# flyback.net
KiCad netlist of a schematic drawn in Altium Designer
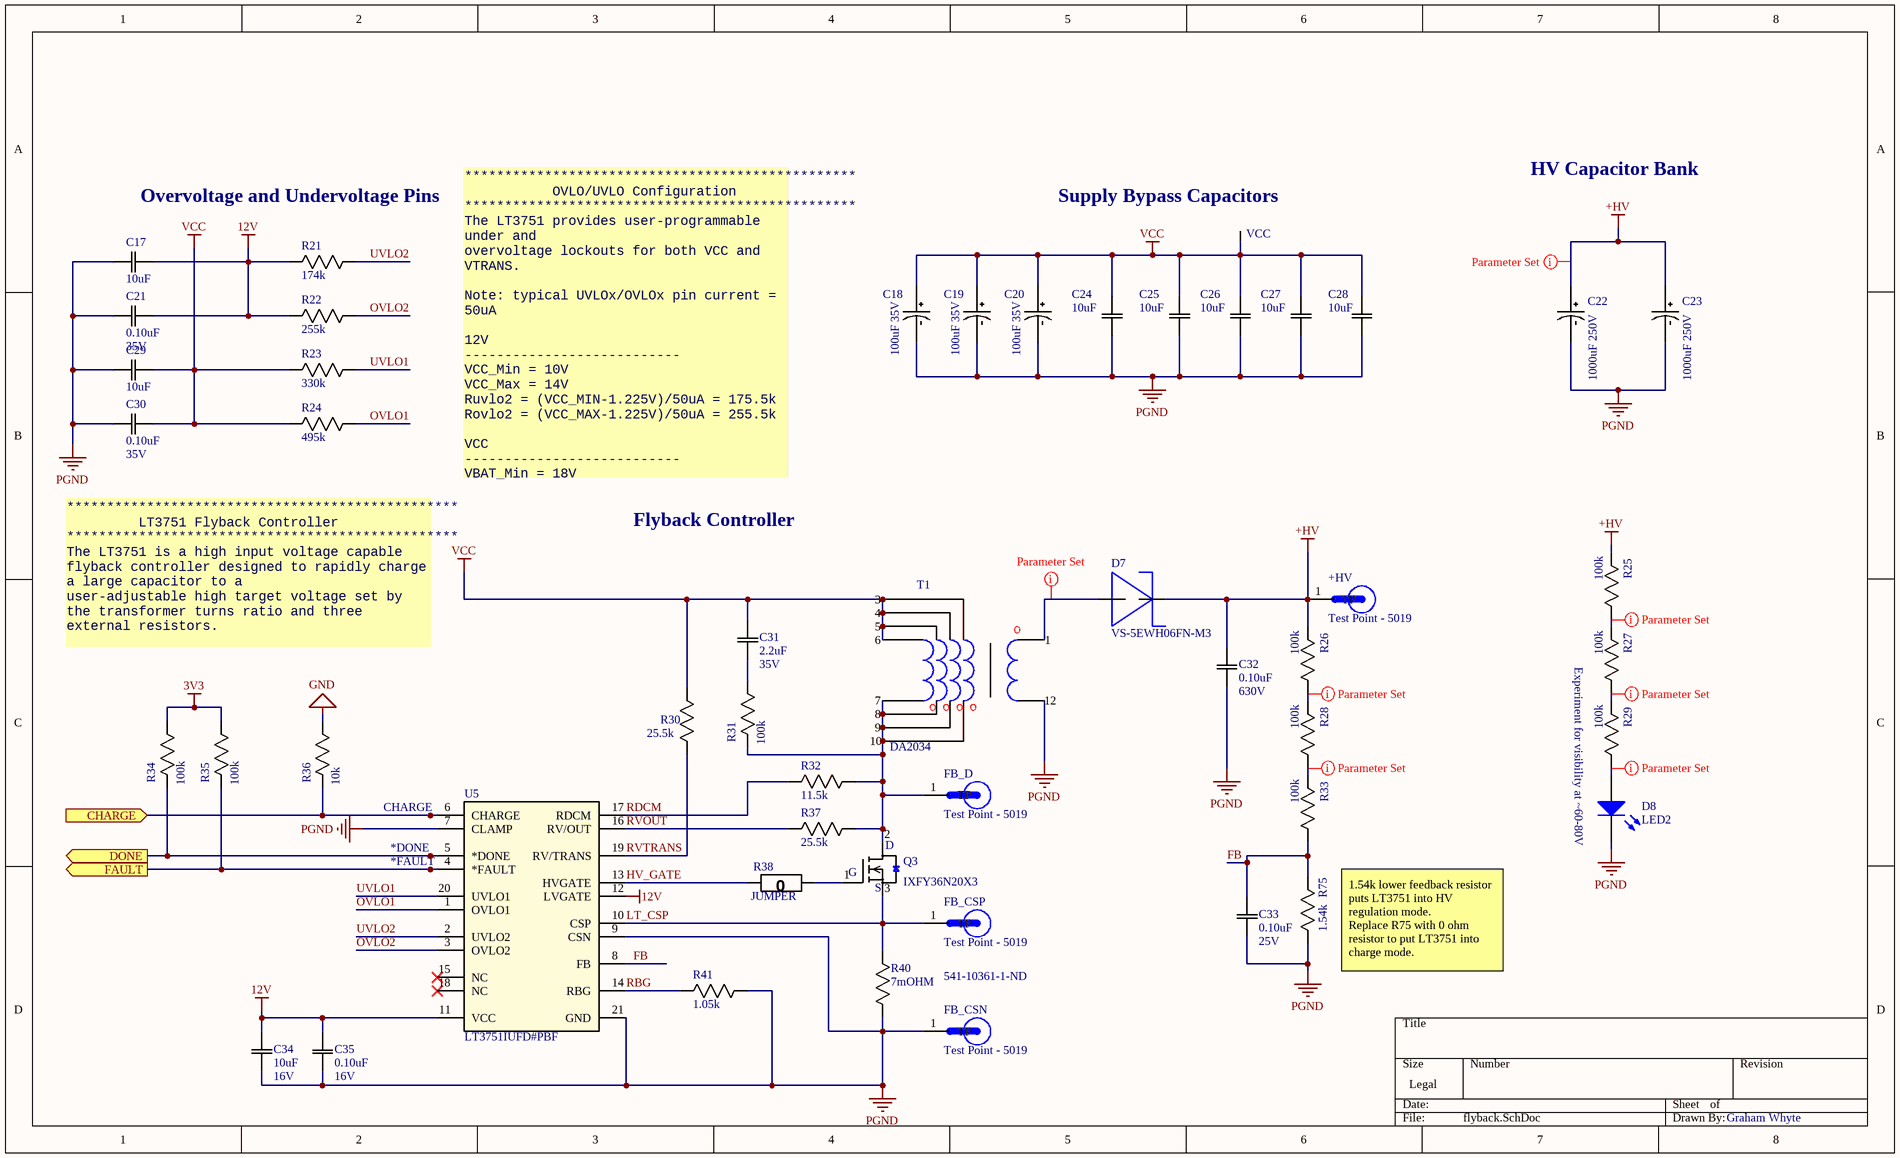
[diagram p0: flyback.SchDoc]

(export (version "E")
  (design (tool "Eeschema 10.0.6"))
  (components
    (comp (ref "*DONE")
      (value "Test Point (Via)")
      (footprint "TP")
      (libsource (lib "IC_Library") (part "Test Point (Via)"))
    )
    (comp (ref "*FAULT")
      (value "Test Point (Via)")
      (footprint "TP")
      (libsource (lib "IC_Library") (part "Test Point (Via)"))
    )
    (comp (ref "+HV")
      (value "Test Point - 5019")
      (footprint "TP380X203")
      (description "PC Test Point, Miniature Phosphor Bronze, Silver Plating Surface Mount Mounting Type")
      (fields (field (name "MP") "5019") (field (name "MF") "Keystone Electronics"))
      (libsource (lib "IC_Library") (part "Test Point - 5019"))
    )
    (comp (ref "C17")
      (value "10uF")
      (footprint "0805")
      (description "CAP CER 10UF 35V X7R 0805")
      (fields (field (name "TOLERANCE") "10%") (field (name "PART NUMBER") "CAP 10uF 35V"))
      (libsource (lib "capacitor_library") (part "CAP 10uF 35V"))
    )
    (comp (ref "C18")
      (value "100uF 35V")
      (footprint "CAP POL ALU 6.3x5.8")
      (description "CAP ALUM 100UF 35V SMD")
      (fields (field (name "TOLERANCE") "20%") (field (name "PART NUMBER") "CAP POL 100uF SMD"))
      (libsource (lib "capacitor_library") (part "CAP POL 100uF SMD"))
    )
    (comp (ref "C19")
      (value "100uF 35V")
      (footprint "CAP POL ALU 6.3x5.8")
      (description "CAP ALUM 100UF 35V SMD")
      (fields (field (name "TOLERANCE") "20%") (field (name "PART NUMBER") "CAP POL 100uF SMD"))
      (libsource (lib "capacitor_library") (part "CAP POL 100uF SMD"))
    )
    (comp (ref "C20")
      (value "100uF 35V")
      (footprint "CAP POL ALU 6.3x5.8")
      (description "CAP ALUM 100UF 35V SMD")
      (fields (field (name "TOLERANCE") "20%") (field (name "PART NUMBER") "CAP POL 100uF SMD"))
      (libsource (lib "capacitor_library") (part "CAP POL 100uF SMD"))
    )
    (comp (ref "C21")
      (value "0.10uF")
      (footprint "0805")
      (description "CAP CER 0.10UF 35V X7R 0805")
      (fields
        (field (name "TOLERANCE") "10%")
        (field (name "RATING") "35V")
        (field (name "PART NUMBER") "CAP 0.10uF 35V")
      )
      (libsource (lib "capacitor_library") (part "CAP 0.10uF 35V"))
    )
    (comp (ref "C22")
      (value "1000uF 250V")
      (footprint "RADIAL, CAN - THRU 25.4mm")
      (description "United Chemi-Con\r\nESMQ251VSN102MQ45S")
      (fields
        (field (name "MANUFACTURER") "United Chemi-Con")
        (field (name "MANUFACTURER PART NUMBER") "ESMQ251VSN102MQ45S")
      )
      (libsource (lib "capacitor_library") (part "CAP POL 1000uF"))
    )
    (comp (ref "C23")
      (value "1000uF 250V")
      (footprint "RADIAL, CAN - THRU 25.4mm")
      (description "United Chemi-Con\r\nESMQ251VSN102MQ45S")
      (fields
        (field (name "MANUFACTURER") "United Chemi-Con")
        (field (name "MANUFACTURER PART NUMBER") "ESMQ251VSN102MQ45S")
      )
      (libsource (lib "capacitor_library") (part "CAP POL 1000uF"))
    )
    (comp (ref "C24")
      (value "10uF")
      (footprint "0805")
      (description "CAP CER 10UF 35V X7R 0805")
      (fields (field (name "TOLERANCE") "10%") (field (name "PART NUMBER") "CAP 10uF 35V"))
      (libsource (lib "capacitor_library") (part "CAP 10uF 35V"))
    )
    (comp (ref "C25")
      (value "10uF")
      (footprint "0805")
      (description "CAP CER 10UF 35V X7R 0805")
      (fields (field (name "TOLERANCE") "10%") (field (name "PART NUMBER") "CAP 10uF 35V"))
      (libsource (lib "capacitor_library") (part "CAP 10uF 35V"))
    )
    (comp (ref "C26")
      (value "10uF")
      (footprint "0805")
      (description "CAP CER 10UF 35V X7R 0805")
      (fields (field (name "TOLERANCE") "10%") (field (name "PART NUMBER") "CAP 10uF 35V"))
      (libsource (lib "capacitor_library") (part "CAP 10uF 35V"))
    )
    (comp (ref "C27")
      (value "10uF")
      (footprint "0805")
      (description "CAP CER 10UF 35V X7R 0805")
      (fields (field (name "TOLERANCE") "10%") (field (name "PART NUMBER") "CAP 10uF 35V"))
      (libsource (lib "capacitor_library") (part "CAP 10uF 35V"))
    )
    (comp (ref "C28")
      (value "10uF")
      (footprint "0805")
      (description "CAP CER 10UF 35V X7R 0805")
      (fields (field (name "TOLERANCE") "10%") (field (name "PART NUMBER") "CAP 10uF 35V"))
      (libsource (lib "capacitor_library") (part "CAP 10uF 35V"))
    )
    (comp (ref "C29")
      (value "10uF")
      (footprint "0805")
      (description "CAP CER 10UF 35V X7R 0805")
      (fields (field (name "TOLERANCE") "10%") (field (name "PART NUMBER") "CAP 10uF 35V"))
      (libsource (lib "capacitor_library") (part "CAP 10uF 35V"))
    )
    (comp (ref "C30")
      (value "0.10uF")
      (footprint "0805")
      (description "CAP CER 0.10UF 35V X7R 0805")
      (fields
        (field (name "TOLERANCE") "10%")
        (field (name "RATING") "35V")
        (field (name "PART NUMBER") "CAP 0.10uF 35V")
      )
      (libsource (lib "capacitor_library") (part "CAP 0.10uF 35V"))
    )
    (comp (ref "C31")
      (value "2.2uF")
      (footprint "0603")
      (description "CAP CER 2.2UF 35V X7R 0603/0805")
      (fields
        (field (name "TOLERANCE") "10%")
        (field (name "RATING") "35V")
        (field (name "PART NUMBER") "CAP 2.2uF 35V")
      )
      (libsource (lib "capacitor_library") (part "CAP 2.2uF 35V"))
    )
    (comp (ref "C32")
      (value "0.10uF")
      (footprint "1210")
      (description "CAP CER 0.1uF 630V X7R 1210")
      (fields
        (field (name "TOLERANCE") "10%")
        (field (name "RATING") "630V")
        (field (name "PART NUMBER") "CAP 0.10uF 630V")
      )
      (libsource (lib "capacitor_library") (part "CAP 0.10uF 630V"))
    )
    (comp (ref "C33")
      (value "0.10uF")
      (footprint "0805")
      (description "CAP CER 0.10UF 25V X7R 0805")
      (fields
        (field (name "TOLERANCE") "10%")
        (field (name "RATING") "25V")
        (field (name "PART NUMBER") "CAP 0.10uF 25V")
      )
      (libsource (lib "capacitor_library") (part "CAP 0.10uF 25V"))
    )
    (comp (ref "C34")
      (value "10uF")
      (footprint "0603")
      (description "CAP CER 10UF 16V X5R 0603/0805")
      (fields
        (field (name "TOLERANCE") "10%")
        (field (name "RATING") "16V")
        (field (name "PART NUMBER") "CAP 10uF 16V")
      )
      (libsource (lib "capacitor_library") (part "CAP 10uF 16V"))
    )
    (comp (ref "C35")
      (value "0.10uF")
      (footprint "0603")
      (description "CAP CER 0.10UF 16V X5R 0603")
      (fields
        (field (name "TOLERANCE") "10%")
        (field (name "RATING") "16V")
        (field (name "PART NUMBER") "CAP 0.10uF 16V")
      )
      (libsource (lib "capacitor_library") (part "CAP 0.10uF 16V"))
    )
    (comp (ref "CHARGE")
      (value "Test Point (Via)")
      (footprint "TP")
      (libsource (lib "IC_Library") (part "Test Point (Via)"))
    )
    (comp (ref "D7")
      (value "VS-5EWH06FN-M3")
      (footprint "DPAK (TO-252)")
      (description "Diode Switching 600V 5A DPAK")
      (fields (field (name "MF") "Vishay Diodes"))
      (libsource (lib "Diode_Library") (part "VS-5EWH06FN-M3"))
    )
    (comp (ref "D8")
      (value "LED2")
      (footprint "3.2X1.6X1.1")
      (description "Typical RED, GREEN, YELLOW, AMBER GaAs LED")
      (fields (field (name "PART NUMBER") "LED GREEN SMD"))
      (libsource (lib "Diode_Library") (part "LED GREEN SMD"))
    )
    (comp (ref "FB_CSN")
      (value "Test Point - 5019")
      (footprint "TP380X203")
      (description "PC Test Point, Miniature Phosphor Bronze, Silver Plating Surface Mount Mounting Type")
      (fields (field (name "MP") "5019") (field (name "MF") "Keystone Electronics"))
      (libsource (lib "IC_Library") (part "Test Point - 5019"))
    )
    (comp (ref "FB_CSP")
      (value "Test Point - 5019")
      (footprint "TP380X203")
      (description "PC Test Point, Miniature Phosphor Bronze, Silver Plating Surface Mount Mounting Type")
      (fields (field (name "MP") "5019") (field (name "MF") "Keystone Electronics"))
      (libsource (lib "IC_Library") (part "Test Point - 5019"))
    )
    (comp (ref "FB_D")
      (value "Test Point - 5019")
      (footprint "TP380X203")
      (description "PC Test Point, Miniature Phosphor Bronze, Silver Plating Surface Mount Mounting Type")
      (fields (field (name "MP") "5019") (field (name "MF") "Keystone Electronics"))
      (libsource (lib "IC_Library") (part "Test Point - 5019"))
    )
    (comp (ref "Q3")
      (value "IXFY36N20X3")
      (footprint "DPAK (TO-252)")
      (description "N-Channel 200 V 36A (Tc) 176W (Tc) Surface Mount TO-252AA")
      (fields (field (name "PART NUMBER") "MOSFET N-CH IXFY36N20X3"))
      (libsource (lib "Transistor_Library") (part "MOSFET N-CH IXFY36N20X3"))
    )
    (comp (ref "R21")
      (value "174k")
      (footprint "0603")
      (description "RES SMD 174K OHM 1% 1/8W 0603")
      (fields
        (field (name "MANUFACTURER") "Yageo")
        (field (name "MANUFACTURER PART NUMBER") "RC0805FR-07174KL")
      )
      (libsource (lib "Resistor_Library") (part "RES 174k 1/8W"))
    )
    (comp (ref "R22")
      (value "255k")
      (footprint "0603")
      (description "RES 255k 1/8W - 1% 0603")
      (fields (field (name "PART NUMBER") "RES 255k 1/8W - 1%"))
      (libsource (lib "Resistor_Library") (part "RES 255k 1/8W - 1%"))
    )
    (comp (ref "R23")
      (value "330k")
      (footprint "0603")
      (description "RES SMD 274K OHM 1% 1/8W 0603")
      (fields (field (name "PART NUMBER") "RES 330k 1/8W - 1%"))
      (libsource (lib "Resistor_Library") (part "RES 330k 1/8W - 1%"))
    )
    (comp (ref "R24")
      (value "495k")
      (footprint "0603")
      (description "RES SMD 495K OHM 1% 1/8W 0603")
      (fields
        (field (name "MANUFACTURER") "Yageo")
        (field (name "MANUFACTURER PART NUMBER") "RC0805FR-07499KL")
      )
      (libsource (lib "Resistor_Library") (part "RES 495k 1/8W"))
    )
    (comp (ref "R25")
      (value "100k")
      (footprint "0603")
      (description "RES SMD 100K OHM 5% 1/8W 0603")
      (fields (field (name "TOLERANCE") "5%") (field (name "PART NUMBER") "RES 100k 1/8W - 5%"))
      (libsource (lib "") (part "RES 100k 1/8W 5%_1"))
    )
    (comp (ref "R26")
      (value "100k")
      (footprint "0603")
      (description "RES SMD 100K OHM 1% 1/8W 0603")
      (fields (field (name "TOLERANCE") "1%") (field (name "PART NUMBER") "RES 100k 1/8W - 1%"))
      (libsource (lib "Resistor_Library") (part "RES 100k 1/8W 1%"))
    )
    (comp (ref "R27")
      (value "100k")
      (footprint "0603")
      (description "RES SMD 100K OHM 5% 1/8W 0603")
      (fields (field (name "TOLERANCE") "5%") (field (name "PART NUMBER") "RES 100k 1/8W - 5%"))
      (libsource (lib "Resistor_Library") (part "RES 100k 1/8W 5%"))
    )
    (comp (ref "R28")
      (value "100k")
      (footprint "0603")
      (description "RES SMD 100K OHM 1% 1/8W 0603")
      (fields (field (name "TOLERANCE") "1%") (field (name "PART NUMBER") "RES 100k 1/8W - 1%"))
      (libsource (lib "") (part "RES 100k 1/8W 1%_1"))
    )
    (comp (ref "R29")
      (value "100k")
      (footprint "0603")
      (description "RES SMD 100K OHM 5% 1/8W 0603")
      (fields (field (name "TOLERANCE") "5%") (field (name "PART NUMBER") "RES 100k 1/8W - 5%"))
      (libsource (lib "Resistor_Library") (part "RES 100k 1/8W 5%"))
    )
    (comp (ref "R30")
      (value "25.5k")
      (footprint "0603")
      (description "RES SMD 25.5K OHM 0.1% 1/8W 0603")
      (fields
        (field (name "MANUFACTURER") "Panasonic")
        (field (name "MANUFACTURER PART NUMBER") "ERA-6AEB2552V")
      )
      (libsource (lib "Resistor_Library") (part "RES 25.5k 1/8W"))
    )
    (comp (ref "R31")
      (value "100k")
      (footprint "0603")
      (description "RES SMD 100K OHM 1% 1/8W 0603")
      (fields (field (name "TOLERANCE") "1%") (field (name "PART NUMBER") "RES 100k 1/8W - 1%"))
      (libsource (lib "Resistor_Library") (part "RES 100k 1/8W 1%"))
    )
    (comp (ref "R32")
      (value "11.5k")
      (footprint "0603")
      (description "RES SMD 11.5K OHM 0.1% 1/8W 0603 Thin Film")
      (fields
        (field (name "MANUFACTURER") "Panasonic")
        (field (name "MANUFACTURER PART NUMBER") "ERA-6AEB1152V")
      )
      (libsource (lib "Resistor_Library") (part "RES 11.5k 1/8W"))
    )
    (comp (ref "R33")
      (value "100k")
      (footprint "0603")
      (description "RES SMD 100K OHM 1% 1/8W 0603")
      (fields (field (name "TOLERANCE") "1%") (field (name "PART NUMBER") "RES 100k 1/8W - 1%"))
      (libsource (lib "") (part "RES 100k 1/8W 1%_1"))
    )
    (comp (ref "R34")
      (value "100k")
      (footprint "0603")
      (description "RES SMD 100K OHM 5% 1/8W 0603")
      (fields (field (name "TOLERANCE") "5%") (field (name "PART NUMBER") "RES 100k 1/8W - 5%"))
      (libsource (lib "Resistor_Library") (part "RES 100k 1/8W 5%"))
    )
    (comp (ref "R35")
      (value "100k")
      (footprint "0603")
      (description "RES SMD 100K OHM 5% 1/8W 0603")
      (fields (field (name "TOLERANCE") "5%") (field (name "PART NUMBER") "RES 100k 1/8W - 5%"))
      (libsource (lib "Resistor_Library") (part "RES 100k 1/8W 5%"))
    )
    (comp (ref "R36")
      (value "10k")
      (footprint "0603")
      (description "RES SMD 10K OHM 5% 1/8W 0603")
      (fields (field (name "TOLERANCE") "5%") (field (name "PART NUMBER") "RES 10k 1/8W - 5%"))
      (libsource (lib "Resistor_Library") (part "RES 10k 1/8W 5%"))
    )
    (comp (ref "R37")
      (value "25.5k")
      (footprint "0603")
      (description "RES SMD 25.5K OHM 0.1% 1/8W 0603")
      (fields
        (field (name "MANUFACTURER") "Panasonic")
        (field (name "MANUFACTURER PART NUMBER") "ERA-6AEB2552V")
      )
      (libsource (lib "Resistor_Library") (part "RES 25.5k 1/8W"))
    )
    (comp (ref "R38")
      (value "JUMPER")
      (footprint "0603")
      (description "RES SMD 0 OHM JUMPER GENERIC 0603")
      (fields (field (name "PART NUMBER") "RES 0 JUMPER"))
      (libsource (lib "Resistor_Library") (part "RES 0 JUMPER"))
    )
    (comp (ref "R40")
      (value "7mOHM")
      (footprint "2512")
      (description "RES SMD 7m OHM 1% 3W 2512")
      (fields
        (field (name "TOLERANCE") "1%")
        (field (name "MFG") "VISHAY")
        (field (name "SUPPLIER PART NUMBER 1") "541-10361-1-ND")
      )
      (libsource (lib "Resistor_Library") (part "RES 7m 3W"))
    )
    (comp (ref "R41")
      (value "1.05k")
      (footprint "0603")
      (description "RES SMD 1.05K OHM 0.1% 1/8W 0603")
      (fields (field (name "TOLERANCE") "0.1%") (field (name "PART NUMBER") "RES 1.05k 1/8W"))
      (libsource (lib "Resistor_Library") (part "RES 1.05k 1/8W"))
    )
    (comp (ref "R75")
      (value "1.54k")
      (footprint "0603")
      (description "RES SMD 1.54k OHM 1% 1/8W 0603")
      (fields (field (name "TOLERANCE") "1%") (field (name "PART NUMBER") "RES 1.54k 1_8W - 1%"))
      (libsource (lib "Resistor_Library") (part "RES 1.54k 1/8W - 1%"))
    )
    (comp (ref "T1")
      (value "DA2034")
      (footprint "DA2034")
      (description "Audio Transformers / Signal Transformers DA2032 Cap Chrgr For Linear LT3750/51")
      (libsource (lib "IC_Library") (part "DA2034"))
    )
    (comp (ref "U5")
      (value "LT3751IUFD#PBF")
      (footprint "QFN-20_UFD_LIT-M")
      (description "IC CTRLR CAP CHRGR 4.75V 20-QFN")
      (fields
        (field (name "MANUFACTURER_PART_NUMBER") "lt3751iufd#pbf")
        (field (name "COPYRIGHT") "Copyright (C) 2021 Ultra Librarian. All rights reserved.")
      )
      (libsource (lib "IC_Library") (part "LT3751IUFD#PBF"))
    )
    (comp (ref "VCC")
      (value "Test Point (Via)")
      (footprint "TP")
      (libsource (lib "IC_Library") (part "Test Point (Via)"))
    )
  )
  (nets
    (net (code "1") (name "+HV") (class "Default")
      (node (ref "+HV") (pin "1") (pinfunction "TP_1") (pintype "passive"))
      (node (ref "C22") (pin "POS") (pinfunction "POS_POS") (pintype "passive"))
      (node (ref "C23") (pin "POS") (pinfunction "POS_POS") (pintype "passive"))
      (node (ref "C32") (pin "1") (pinfunction "C1_1") (pintype "passive"))
      (node (ref "D7") (pin "OUT") (pinfunction "OUT_OUT") (pintype "passive"))
      (node (ref "R25") (pin "2") (pinfunction "R2_2") (pintype "passive"))
      (node (ref "R26") (pin "2") (pinfunction "R2_2") (pintype "passive"))
    )
    (net (code "3") (name "/CHARGE") (class "Default")
      (node (ref "CHARGE") (pin "1") (pinfunction "1_1") (pintype "passive"))
      (node (ref "R36") (pin "2") (pinfunction "R2_2") (pintype "passive"))
      (node (ref "U5") (pin "6") (pinfunction "CHARGE_6") (pintype "passive"))
    )
    (net (code "4") (name "/DONE") (class "Default")
      (node (ref "*DONE") (pin "1") (pinfunction "1_1") (pintype "passive"))
      (node (ref "R34") (pin "2") (pinfunction "R2_2") (pintype "passive"))
      (node (ref "U5") (pin "5") (pinfunction "*DONE_5") (pintype "passive"))
    )
    (net (code "5") (name "/FAULT") (class "Default")
      (node (ref "*FAULT") (pin "1") (pinfunction "1_1") (pintype "passive"))
      (node (ref "R35") (pin "2") (pinfunction "R2_2") (pintype "passive"))
      (node (ref "U5") (pin "4") (pinfunction "*FAULT_4") (pintype "passive"))
    )
    (net (code "6") (name "/FB") (class "Default")
      (node (ref "C33") (pin "1") (pinfunction "C1_1") (pintype "passive"))
      (node (ref "R33") (pin "1") (pinfunction "R1_1") (pintype "passive"))
      (node (ref "R75") (pin "2") (pinfunction "R2_2") (pintype "passive"))
      (node (ref "U5") (pin "8") (pinfunction "FB_8") (pintype "passive"))
    )
    (net (code "7") (name "/HV_GATE") (class "Default")
      (node (ref "R38") (pin "2") (pinfunction "R2_2") (pintype "passive"))
      (node (ref "U5") (pin "13") (pinfunction "HVGATE_13") (pintype "passive"))
    )
    (net (code "8") (name "/LT_CSP") (class "Default")
      (node (ref "FB_CSP") (pin "1") (pinfunction "TP_1") (pintype "passive"))
      (node (ref "Q3") (pin "3") (pinfunction "S_3") (pintype "passive"))
      (node (ref "R40") (pin "2") (pinfunction "R2_2") (pintype "passive"))
      (node (ref "U5") (pin "10") (pinfunction "CSP_10") (pintype "passive"))
    )
    (net (code "9") (name "/OVLO1") (class "Default")
      (node (ref "R24") (pin "1") (pinfunction "R1_1") (pintype "passive"))
      (node (ref "U5") (pin "1") (pinfunction "OVLO1_1") (pintype "passive"))
    )
    (net (code "10") (name "/OVLO2") (class "Default")
      (node (ref "R22") (pin "1") (pinfunction "R1_1") (pintype "passive"))
      (node (ref "U5") (pin "3") (pinfunction "OVLO2_3") (pintype "passive"))
    )
    (net (code "11") (name "/RBG") (class "Default")
      (node (ref "R41") (pin "2") (pinfunction "R2_2") (pintype "passive"))
      (node (ref "U5") (pin "14") (pinfunction "RBG_14") (pintype "passive"))
    )
    (net (code "12") (name "/RDCM") (class "Default")
      (node (ref "R32") (pin "2") (pinfunction "R2_2") (pintype "passive"))
      (node (ref "U5") (pin "17") (pinfunction "RDCM_17") (pintype "passive"))
    )
    (net (code "13") (name "/RVOUT") (class "Default")
      (node (ref "R37") (pin "2") (pinfunction "R2_2") (pintype "passive"))
      (node (ref "U5") (pin "16") (pinfunction "RV/OUT_16") (pintype "passive"))
    )
    (net (code "14") (name "/RVTRANS") (class "Default")
      (node (ref "R30") (pin "2") (pinfunction "R2_2") (pintype "passive"))
      (node (ref "U5") (pin "19") (pinfunction "RV/TRANS_19") (pintype "passive"))
    )
    (net (code "15") (name "/UVLO1") (class "Default")
      (node (ref "R23") (pin "1") (pinfunction "R1_1") (pintype "passive"))
      (node (ref "U5") (pin "20") (pinfunction "UVLO1_20") (pintype "passive"))
    )
    (net (code "16") (name "/UVLO2") (class "Default")
      (node (ref "R21") (pin "1") (pinfunction "R1_1") (pintype "passive"))
      (node (ref "U5") (pin "2") (pinfunction "UVLO2_2") (pintype "passive"))
    )
    (net (code "17") (name "3V3") (class "Default")
      (node (ref "R34") (pin "1") (pinfunction "R1_1") (pintype "passive"))
      (node (ref "R35") (pin "1") (pinfunction "R1_1") (pintype "passive"))
    )
    (net (code "18") (name "12V") (class "Default")
      (node (ref "C17") (pin "2") (pinfunction "C2_2") (pintype "passive"))
      (node (ref "C21") (pin "2") (pinfunction "C2_2") (pintype "passive"))
      (node (ref "C34") (pin "1") (pinfunction "C1_1") (pintype "passive"))
      (node (ref "C35") (pin "2") (pinfunction "C2_2") (pintype "passive"))
      (node (ref "R21") (pin "2") (pinfunction "R2_2") (pintype "passive"))
      (node (ref "R22") (pin "2") (pinfunction "R2_2") (pintype "passive"))
      (node (ref "U5") (pin "11") (pinfunction "VCC_11") (pintype "power_in"))
      (node (ref "U5") (pin "12") (pinfunction "LVGATE_12") (pintype "passive"))
    )
    (net (code "19") (name "GND") (class "Default")
      (node (ref "R36") (pin "1") (pinfunction "R1_1") (pintype "passive"))
    )
    (net (code "20") (name "Net-(C31-C1)") (class "Default")
      (node (ref "C31") (pin "1") (pinfunction "C1_1") (pintype "passive"))
      (node (ref "R31") (pin "1") (pinfunction "R1_1") (pintype "passive"))
    )
    (net (code "21") (name "Net-(D7-PadIN)") (class "Default")
      (node (ref "D7") (pin "IN") (pinfunction "IN_IN") (pintype "passive"))
      (node (ref "T1") (pin "1") (pinfunction "1_1") (pintype "passive"))
    )
    (net (code "22") (name "Net-(D8-A)") (class "Default")
      (node (ref "D8") (pin "1") (pinfunction "A_1") (pintype "passive"))
      (node (ref "R29") (pin "1") (pinfunction "R1_1") (pintype "passive"))
    )
    (net (code "23") (name "Net-(FB_D-TP)") (class "Default")
      (node (ref "FB_D") (pin "1") (pinfunction "TP_1") (pintype "passive"))
      (node (ref "Q3") (pin "2") (pinfunction "D_2") (pintype "passive"))
      (node (ref "R31") (pin "2") (pinfunction "R2_2") (pintype "passive"))
      (node (ref "R32") (pin "1") (pinfunction "R1_1") (pintype "passive"))
      (node (ref "R37") (pin "1") (pinfunction "R1_1") (pintype "passive"))
      (node (ref "T1") (pin "10") (pinfunction "10_10") (pintype "passive"))
      (node (ref "T1") (pin "7") (pinfunction "7_7") (pintype "passive"))
      (node (ref "T1") (pin "8") (pinfunction "8_8") (pintype "passive"))
      (node (ref "T1") (pin "9") (pinfunction "9_9") (pintype "passive"))
    )
    (net (code "24") (name "Net-(Q3-G)") (class "Default")
      (node (ref "Q3") (pin "1") (pinfunction "G_1") (pintype "passive"))
      (node (ref "R38") (pin "1") (pinfunction "R1_1") (pintype "passive"))
    )
    (net (code "25") (name "Net-(R25-R1)") (class "Default")
      (node (ref "R25") (pin "1") (pinfunction "R1_1") (pintype "passive"))
      (node (ref "R27") (pin "2") (pinfunction "R2_2") (pintype "passive"))
    )
    (net (code "26") (name "Net-(R26-R1)") (class "Default")
      (node (ref "R26") (pin "1") (pinfunction "R1_1") (pintype "passive"))
      (node (ref "R28") (pin "2") (pinfunction "R2_2") (pintype "passive"))
    )
    (net (code "27") (name "Net-(R27-R1)") (class "Default")
      (node (ref "R27") (pin "1") (pinfunction "R1_1") (pintype "passive"))
      (node (ref "R29") (pin "2") (pinfunction "R2_2") (pintype "passive"))
    )
    (net (code "28") (name "Net-(R28-R1)") (class "Default")
      (node (ref "R28") (pin "1") (pinfunction "R1_1") (pintype "passive"))
      (node (ref "R33") (pin "2") (pinfunction "R2_2") (pintype "passive"))
    )
    (net (code "29") (name "PGND") (class "Default")
      (node (ref "C17") (pin "1") (pinfunction "C1_1") (pintype "passive"))
      (node (ref "C18") (pin "NEG") (pinfunction "NEG_NEG") (pintype "passive"))
      (node (ref "C19") (pin "NEG") (pinfunction "NEG_NEG") (pintype "passive"))
      (node (ref "C20") (pin "NEG") (pinfunction "NEG_NEG") (pintype "passive"))
      (node (ref "C21") (pin "1") (pinfunction "C1_1") (pintype "passive"))
      (node (ref "C22") (pin "NEG") (pinfunction "NEG_NEG") (pintype "passive"))
      (node (ref "C23") (pin "NEG") (pinfunction "NEG_NEG") (pintype "passive"))
      (node (ref "C24") (pin "1") (pinfunction "C1_1") (pintype "passive"))
      (node (ref "C25") (pin "1") (pinfunction "C1_1") (pintype "passive"))
      (node (ref "C26") (pin "1") (pinfunction "C1_1") (pintype "passive"))
      (node (ref "C27") (pin "1") (pinfunction "C1_1") (pintype "passive"))
      (node (ref "C28") (pin "1") (pinfunction "C1_1") (pintype "passive"))
      (node (ref "C29") (pin "1") (pinfunction "C1_1") (pintype "passive"))
      (node (ref "C30") (pin "1") (pinfunction "C1_1") (pintype "passive"))
      (node (ref "C32") (pin "2") (pinfunction "C2_2") (pintype "passive"))
      (node (ref "C33") (pin "2") (pinfunction "C2_2") (pintype "passive"))
      (node (ref "C34") (pin "2") (pinfunction "C2_2") (pintype "passive"))
      (node (ref "C35") (pin "1") (pinfunction "C1_1") (pintype "passive"))
      (node (ref "D8") (pin "2") (pinfunction "K_2") (pintype "passive"))
      (node (ref "FB_CSN") (pin "1") (pinfunction "TP_1") (pintype "passive"))
      (node (ref "R40") (pin "1") (pinfunction "R1_1") (pintype "passive"))
      (node (ref "R41") (pin "1") (pinfunction "R1_1") (pintype "passive"))
      (node (ref "R75") (pin "1") (pinfunction "R1_1") (pintype "passive"))
      (node (ref "T1") (pin "12") (pinfunction "12_12") (pintype "passive"))
      (node (ref "U5") (pin "21") (pinfunction "GND_21") (pintype "passive"))
      (node (ref "U5") (pin "7") (pinfunction "CLAMP_7") (pintype "passive"))
      (node (ref "U5") (pin "9") (pinfunction "CSN_9") (pintype "passive"))
    )
    (net (code "30") (name "VCC") (class "Default")
      (node (ref "C18") (pin "POS") (pinfunction "POS_POS") (pintype "passive"))
      (node (ref "C19") (pin "POS") (pinfunction "POS_POS") (pintype "passive"))
      (node (ref "C20") (pin "POS") (pinfunction "POS_POS") (pintype "passive"))
      (node (ref "C24") (pin "2") (pinfunction "C2_2") (pintype "passive"))
      (node (ref "C25") (pin "2") (pinfunction "C2_2") (pintype "passive"))
      (node (ref "C26") (pin "2") (pinfunction "C2_2") (pintype "passive"))
      (node (ref "C27") (pin "2") (pinfunction "C2_2") (pintype "passive"))
      (node (ref "C28") (pin "2") (pinfunction "C2_2") (pintype "passive"))
      (node (ref "C29") (pin "2") (pinfunction "C2_2") (pintype "passive"))
      (node (ref "C30") (pin "2") (pinfunction "C2_2") (pintype "passive"))
      (node (ref "C31") (pin "2") (pinfunction "C2_2") (pintype "passive"))
      (node (ref "R23") (pin "2") (pinfunction "R2_2") (pintype "passive"))
      (node (ref "R24") (pin "2") (pinfunction "R2_2") (pintype "passive"))
      (node (ref "R30") (pin "1") (pinfunction "R1_1") (pintype "passive"))
      (node (ref "T1") (pin "3") (pinfunction "3_3") (pintype "passive"))
      (node (ref "T1") (pin "4") (pinfunction "4_4") (pintype "passive"))
      (node (ref "T1") (pin "5") (pinfunction "5_5") (pintype "passive"))
      (node (ref "T1") (pin "6") (pinfunction "6_6") (pintype "passive"))
      (node (ref "VCC") (pin "1") (pinfunction "1_1") (pintype "passive"))
    )
    (net (code "31") (name "unconnected-(U5-NC-Pad15)") (class "Default")
      (node (ref "U5") (pin "15") (pinfunction "NC_15") (pintype "passive+no_connect"))
    )
    (net (code "32") (name "unconnected-(U5-NC-Pad18)") (class "Default")
      (node (ref "U5") (pin "18") (pinfunction "NC_18") (pintype "passive+no_connect"))
    )
  )
)
